# powerBus_Sch.net
KiCad netlist of a schematic drawn in Altium Designer
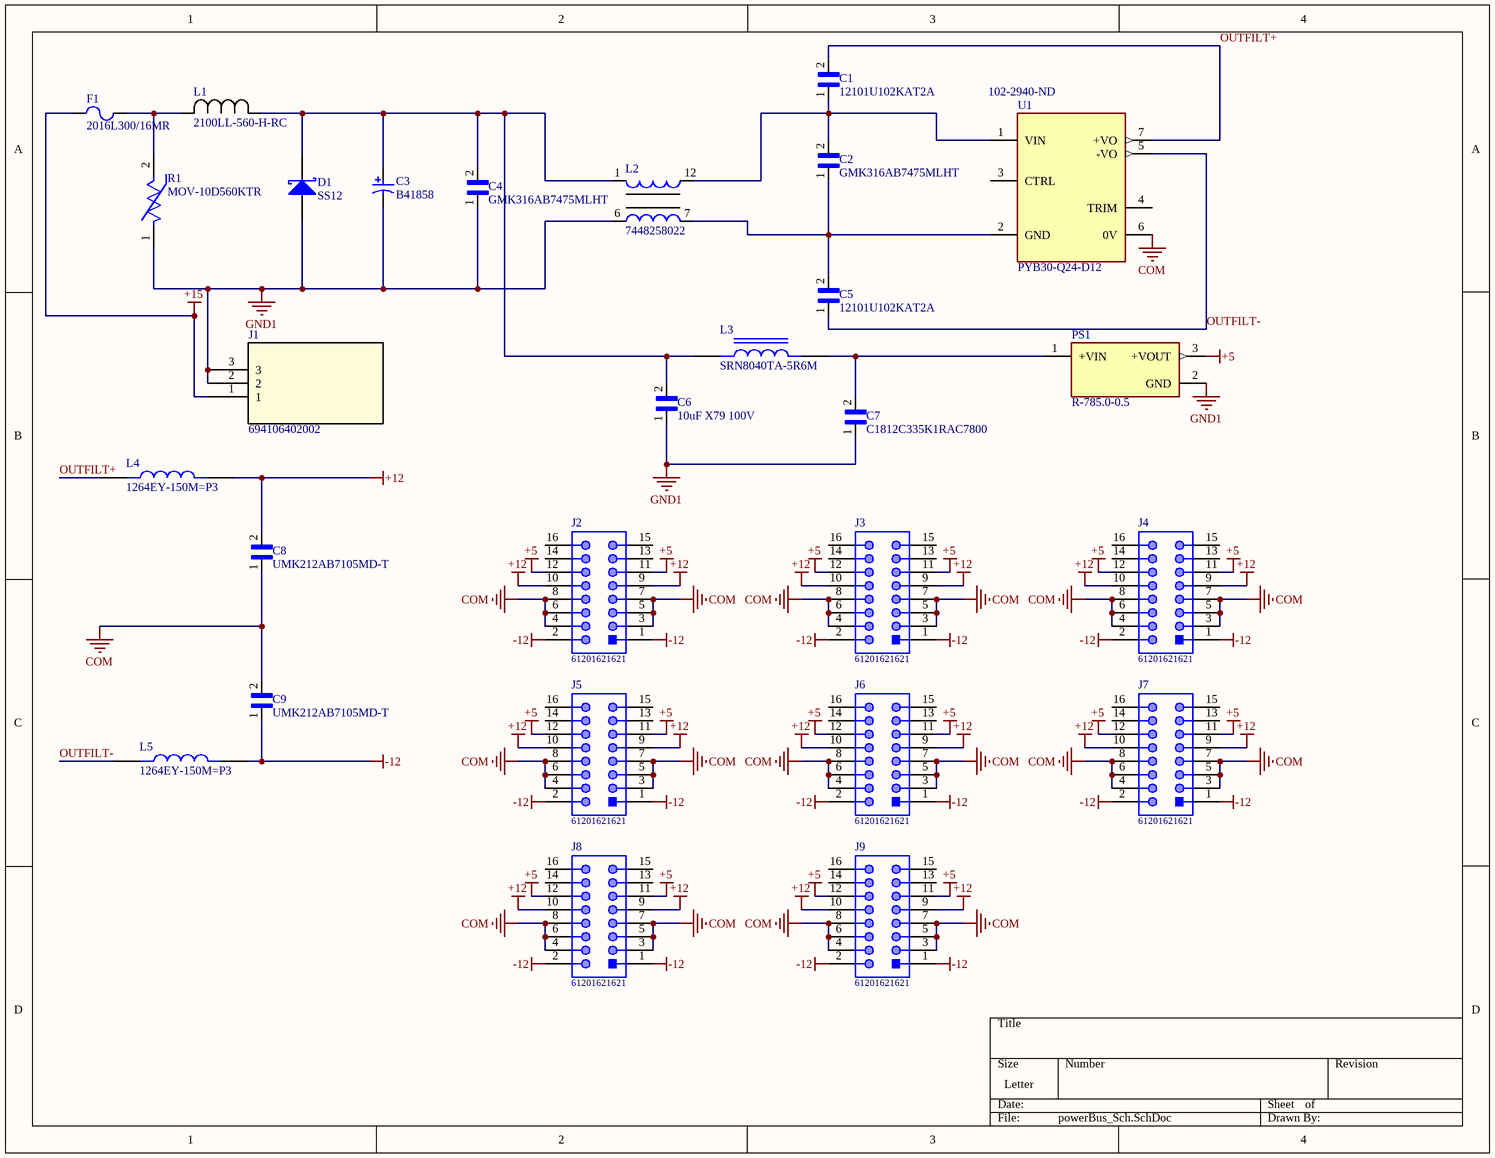
[diagram p0: powerBus_Sch.SchDoc]

(export (version "E")
  (design (tool "Eeschema 10.0.6"))
  (components
    (comp (ref "C1")
      (value "12101U102KAT2A")
      (footprint "CAPC3224X140N")
      (description "1210 1 nF 100 V Â±10 % Tolerance SMT Ultra Low ESR RF/Microwave Capacitor")
      (libsource (lib "1000pf_NP0_lowesr_1210") (part "12101U102KAT2A"))
    )
    (comp (ref "C2")
      (value "GMK316AB7475MLHT")
      (footprint "CAPC3216X180N")
      (description "0")
      (libsource (lib "4R7_X7R_1206_GMK316AB7475MLHT") (part "GMK316AB7475MLHT"))
    )
    (comp (ref "C3")
      (value "B41858")
      (footprint "CAPPR65-350-1150X800X1250")
      (description "Aluminum Electrolytic Capacitor, 120uF")
      (libsource (lib "Altium Content Vault") (part "CAP-P-2"))
    )
    (comp (ref "C4")
      (value "GMK316AB7475MLHT")
      (footprint "CAPC3216X180N")
      (description "0")
      (libsource (lib "4R7_X7R_1206_GMK316AB7475MLHT") (part "GMK316AB7475MLHT"))
    )
    (comp (ref "C5")
      (value "12101U102KAT2A")
      (footprint "CAPC3224X140N")
      (description "1210 1 nF 100 V Â±10 % Tolerance SMT Ultra Low ESR RF/Microwave Capacitor")
      (libsource (lib "1000pf_NP0_lowesr_1210") (part "12101U102KAT2A"))
    )
    (comp (ref "C6")
      (value "10uF X79 100V")
      (footprint "CAPC5750X330N")
      (fields (field (name "MP") "C1812C335K1RAC7800"))
      (libsource (lib "3.3uF_kemet_x7R_C1812C335K1RAC7800") (part "C1812C335K1RAC7800"))
    )
    (comp (ref "C7")
      (value "C1812C335K1RAC7800")
      (footprint "CAPC4532X210N")
      (libsource (lib "3.3uF_kemet_x7R_C1812C335K1RAC7800") (part "C1812C335K1RAC7800"))
    )
    (comp (ref "C8")
      (value "UMK212AB7105MD-T")
      (footprint "CAPC2013X95N")
      (description "CAP ,MLCC ,0805,50V ,X7R,1.0UF20% ,T&R")
      (libsource (lib "1uF_X7R_low_esr_UMK212AB7105MD-T") (part "UMK212AB7105MD-T"))
    )
    (comp (ref "C9")
      (value "UMK212AB7105MD-T")
      (footprint "CAPC2013X95N")
      (description "CAP ,MLCC ,0805,50V ,X7R,1.0UF20% ,T&R")
      (libsource (lib "1uF_X7R_low_esr_UMK212AB7105MD-T") (part "UMK212AB7105MD-T"))
    )
    (comp (ref "D1")
      (value "SS12")
      (footprint "FAIR-DO-214AC-2_V")
      (description "Schottky Rectifier, 20 V, 1 A, -65 to 125 degC, 2-Pin DO-214AC, RoHS, Tape and Reel")
      (fields (field (name "MANUFACTURER") "Fairchild"))
      (libsource (lib "Ryan Laur") (part "DSKY-AK-2"))
    )
    (comp (ref "F1")
      (value "2016L300/16MR")
      (footprint "LFUS-2016L050MR_V")
      (description "Poly-Fuse(R) Resettable PTC, 60 V, 20 A, -40 to 85 degC, 2-Pin SMD, RoHS, Tape and Reel")
      (fields (field (name "MANUFACTURER") "Littelfuse"))
      (libsource (lib "Altium Content Vault") (part "FUSE-2"))
    )
    (comp (ref "J1")
      (value "694106402002")
      (footprint "DC_JACK")
      (description "No Description Available")
      (fields (field (name "COPYRIGHT") "Copyright (C) 2022 Ultra Librarian. All rights reserved."))
      (libsource (lib "wurth_dc_jack_694106402002") (part "694106402002"))
    )
    (comp (ref "J2")
      (value "61201621621")
      (footprint "61201621621")
      (description "Male Box Header WR-BHD, THT, Vertical, pitch 2.54 mm, 16 pins")
      (fields (field (name "MANUFACTURER") "Wurth Elektronik") (field (name "PUBLISHER") "WurthElektronik"))
      (libsource (lib "Altium Content Vault") (part "WE-CN-2P-M-R16"))
    )
    (comp (ref "J3")
      (value "61201621621")
      (footprint "61201621621")
      (description "Male Box Header WR-BHD, THT, Vertical, pitch 2.54 mm, 16 pins")
      (fields (field (name "MANUFACTURER") "Wurth Elektronik") (field (name "PUBLISHER") "WurthElektronik"))
      (libsource (lib "Altium Content Vault") (part "WE-CN-2P-M-R16"))
    )
    (comp (ref "J4")
      (value "61201621621")
      (footprint "61201621621")
      (description "Male Box Header WR-BHD, THT, Vertical, pitch 2.54 mm, 16 pins")
      (fields (field (name "MANUFACTURER") "Wurth Elektronik") (field (name "PUBLISHER") "WurthElektronik"))
      (libsource (lib "Altium Content Vault") (part "WE-CN-2P-M-R16"))
    )
    (comp (ref "J5")
      (value "61201621621")
      (footprint "61201621621")
      (description "Male Box Header WR-BHD, THT, Vertical, pitch 2.54 mm, 16 pins")
      (fields (field (name "MANUFACTURER") "Wurth Elektronik") (field (name "PUBLISHER") "WurthElektronik"))
      (libsource (lib "Altium Content Vault") (part "WE-CN-2P-M-R16"))
    )
    (comp (ref "J6")
      (value "61201621621")
      (footprint "61201621621")
      (description "Male Box Header WR-BHD, THT, Vertical, pitch 2.54 mm, 16 pins")
      (fields (field (name "MANUFACTURER") "Wurth Elektronik") (field (name "PUBLISHER") "WurthElektronik"))
      (libsource (lib "Altium Content Vault") (part "WE-CN-2P-M-R16"))
    )
    (comp (ref "J7")
      (value "61201621621")
      (footprint "61201621621")
      (description "Male Box Header WR-BHD, THT, Vertical, pitch 2.54 mm, 16 pins")
      (fields (field (name "MANUFACTURER") "Wurth Elektronik") (field (name "PUBLISHER") "WurthElektronik"))
      (libsource (lib "Altium Content Vault") (part "WE-CN-2P-M-R16"))
    )
    (comp (ref "J8")
      (value "61201621621")
      (footprint "61201621621")
      (description "Male Box Header WR-BHD, THT, Vertical, pitch 2.54 mm, 16 pins")
      (fields (field (name "MANUFACTURER") "Wurth Elektronik") (field (name "PUBLISHER") "WurthElektronik"))
      (libsource (lib "Altium Content Vault") (part "WE-CN-2P-M-R16"))
    )
    (comp (ref "J9")
      (value "61201621621")
      (footprint "61201621621")
      (description "Male Box Header WR-BHD, THT, Vertical, pitch 2.54 mm, 16 pins")
      (fields (field (name "MANUFACTURER") "Wurth Elektronik") (field (name "PUBLISHER") "WurthElektronik"))
      (libsource (lib "Altium Content Vault") (part "WE-CN-2P-M-R16"))
    )
    (comp (ref "L1")
      (value "2100LL-560-H-RC")
      (footprint "IND_2100LL_34_H")
      (description "No Description Available")
      (fields (field (name "COPYRIGHT") "Copyright (C) 2022 Ultra Librarian. All rights reserved."))
      (libsource (lib "2100LL-560-H-RC") (part "2100LL-560-H-RC"))
    )
    (comp (ref "L2")
      (value "7448258022")
      (footprint "WE-CMB-XL")
      (description "THT Common Mode Power Line Choke WE-CMB, L = 2.20 mH")
      (libsource (lib "Altium Content Vault") (part "PAS-IND-INDUCTOR-4G"))
    )
    (comp (ref "L3")
      (value "SRN8040TA-5R6M")
      (footprint "IND_SRN8040TA-5R6M")
      (libsource (lib "SRN8040TA-5R6M") (part "SRN8040TA-5R6M"))
    )
    (comp (ref "L4")
      (value "1264EY-150M=P3")
      (footprint "IND_1264EY-150M=P3")
      (description "Inductor Power Shielded Wirewound 22uH 20% 100KHz Ferrite 1.8A 132mOhm DCR 2424 T/R")
      (libsource (lib "murata_15uh_ferrite_ind_1264EY-150M_P3") (part "1264EY-150M=P3"))
    )
    (comp (ref "L5")
      (value "1264EY-150M=P3")
      (footprint "IND_1264EY-150M=P3")
      (description "Inductor Power Shielded Wirewound 22uH 20% 100KHz Ferrite 1.8A 132mOhm DCR 2424 T/R")
      (libsource (lib "murata_15uh_ferrite_ind_1264EY-150M_P3") (part "1264EY-150M=P3"))
    )
    (comp (ref "PS1")
      (value "R-785.0-0.5")
      (footprint "CONV_R-785.0-0.5")
      (description "0.5A DC/DC-Converter 'INNOLINE' SIP3 reg")
      (fields (field (name "MF") "Recom Power"))
      (libsource (lib "Recom-785.0 5V-0.5A") (part "R-785.0-0.5"))
    )
    (comp (ref "R1")
      (value "MOV-10D560KTR")
      (footprint "FP-MOV-10D201KTR-MFG")
      (description "VARISTOR 200V 2.5KA DISC 10MM")
      (fields
        (field (name "MANUFACTURER") "Bourns Inc.")
        (field (name "OCTOPART") "https://octopart.com/mov-10d201ktr-bourns-19184757")
      )
      (libsource (lib "Altium Content Vault") (part "78a88060d5b7b043d6e48adc4284376"))
    )
    (comp (ref "U1")
      (value "PYB30-Q24-D12")
      (footprint "CONV_PYB30-Q24-D12")
      (description "12/-12 Vdc, 1.25 A, 30 W, 9~36 Vdc Input Range")
      (fields (field (name "SUPPLIER PART NUMBER 1") "102-2940-ND"))
      (libsource (lib "DC_Conv_PYB30-Q24-D12") (part "PYB30-Q24-D12"))
    )
  )
  (nets
    (net (code "1") (name "+5") (class "Default")
      (node (ref "J2") (pin "11") (pinfunction "11_11") (pintype "passive"))
      (node (ref "J2") (pin "12") (pinfunction "12_12") (pintype "passive"))
      (node (ref "J3") (pin "11") (pinfunction "11_11") (pintype "passive"))
      (node (ref "J3") (pin "12") (pinfunction "12_12") (pintype "passive"))
      (node (ref "J4") (pin "11") (pinfunction "11_11") (pintype "passive"))
      (node (ref "J4") (pin "12") (pinfunction "12_12") (pintype "passive"))
      (node (ref "J5") (pin "11") (pinfunction "11_11") (pintype "passive"))
      (node (ref "J5") (pin "12") (pinfunction "12_12") (pintype "passive"))
      (node (ref "J6") (pin "11") (pinfunction "11_11") (pintype "passive"))
      (node (ref "J6") (pin "12") (pinfunction "12_12") (pintype "passive"))
      (node (ref "J7") (pin "11") (pinfunction "11_11") (pintype "passive"))
      (node (ref "J7") (pin "12") (pinfunction "12_12") (pintype "passive"))
      (node (ref "J8") (pin "11") (pinfunction "11_11") (pintype "passive"))
      (node (ref "J8") (pin "12") (pinfunction "12_12") (pintype "passive"))
      (node (ref "J9") (pin "11") (pinfunction "11_11") (pintype "passive"))
      (node (ref "J9") (pin "12") (pinfunction "12_12") (pintype "passive"))
      (node (ref "PS1") (pin "3") (pinfunction "+VOUT_3") (pintype "output"))
    )
    (net (code "2") (name "+12") (class "Default")
      (node (ref "C8") (pin "2") (pinfunction "2_2") (pintype "passive"))
      (node (ref "J2") (pin "10") (pinfunction "10_10") (pintype "passive"))
      (node (ref "J2") (pin "9") (pinfunction "9_9") (pintype "passive"))
      (node (ref "J3") (pin "10") (pinfunction "10_10") (pintype "passive"))
      (node (ref "J3") (pin "9") (pinfunction "9_9") (pintype "passive"))
      (node (ref "J4") (pin "10") (pinfunction "10_10") (pintype "passive"))
      (node (ref "J4") (pin "9") (pinfunction "9_9") (pintype "passive"))
      (node (ref "J5") (pin "10") (pinfunction "10_10") (pintype "passive"))
      (node (ref "J5") (pin "9") (pinfunction "9_9") (pintype "passive"))
      (node (ref "J6") (pin "10") (pinfunction "10_10") (pintype "passive"))
      (node (ref "J6") (pin "9") (pinfunction "9_9") (pintype "passive"))
      (node (ref "J7") (pin "10") (pinfunction "10_10") (pintype "passive"))
      (node (ref "J7") (pin "9") (pinfunction "9_9") (pintype "passive"))
      (node (ref "J8") (pin "10") (pinfunction "10_10") (pintype "passive"))
      (node (ref "J8") (pin "9") (pinfunction "9_9") (pintype "passive"))
      (node (ref "J9") (pin "10") (pinfunction "10_10") (pintype "passive"))
      (node (ref "J9") (pin "9") (pinfunction "9_9") (pintype "passive"))
      (node (ref "L4") (pin "2") (pinfunction "2_2") (pintype "passive"))
    )
    (net (code "3") (name "+15") (class "Default")
      (node (ref "F1") (pin "1") (pinfunction "1_1") (pintype "passive"))
      (node (ref "J1") (pin "1") (pinfunction "1_1") (pintype "passive"))
    )
    (net (code "4") (name "-12") (class "Default")
      (node (ref "C9") (pin "1") (pinfunction "1_1") (pintype "passive"))
      (node (ref "J2") (pin "1") (pinfunction "1_1") (pintype "passive"))
      (node (ref "J2") (pin "2") (pinfunction "2_2") (pintype "passive"))
      (node (ref "J3") (pin "1") (pinfunction "1_1") (pintype "passive"))
      (node (ref "J3") (pin "2") (pinfunction "2_2") (pintype "passive"))
      (node (ref "J4") (pin "1") (pinfunction "1_1") (pintype "passive"))
      (node (ref "J4") (pin "2") (pinfunction "2_2") (pintype "passive"))
      (node (ref "J5") (pin "1") (pinfunction "1_1") (pintype "passive"))
      (node (ref "J5") (pin "2") (pinfunction "2_2") (pintype "passive"))
      (node (ref "J6") (pin "1") (pinfunction "1_1") (pintype "passive"))
      (node (ref "J6") (pin "2") (pinfunction "2_2") (pintype "passive"))
      (node (ref "J7") (pin "1") (pinfunction "1_1") (pintype "passive"))
      (node (ref "J7") (pin "2") (pinfunction "2_2") (pintype "passive"))
      (node (ref "J8") (pin "1") (pinfunction "1_1") (pintype "passive"))
      (node (ref "J8") (pin "2") (pinfunction "2_2") (pintype "passive"))
      (node (ref "J9") (pin "1") (pinfunction "1_1") (pintype "passive"))
      (node (ref "J9") (pin "2") (pinfunction "2_2") (pintype "passive"))
      (node (ref "L5") (pin "2") (pinfunction "2_2") (pintype "passive"))
    )
    (net (code "5") (name "/OUTFILT+") (class "Default")
      (node (ref "C1") (pin "2") (pinfunction "2_2") (pintype "passive"))
      (node (ref "L4") (pin "1") (pinfunction "1_1") (pintype "passive"))
      (node (ref "U1") (pin "7") (pinfunction "+VO_7") (pintype "output"))
    )
    (net (code "6") (name "/OUTFILT-") (class "Default")
      (node (ref "C5") (pin "1") (pinfunction "1_1") (pintype "passive"))
      (node (ref "L5") (pin "1") (pinfunction "1_1") (pintype "passive"))
      (node (ref "U1") (pin "5") (pinfunction "-VO_5") (pintype "output"))
    )
    (net (code "7") (name "COM") (class "Default")
      (node (ref "C8") (pin "1") (pinfunction "1_1") (pintype "passive"))
      (node (ref "C9") (pin "2") (pinfunction "2_2") (pintype "passive"))
      (node (ref "J2") (pin "3") (pinfunction "3_3") (pintype "passive"))
      (node (ref "J2") (pin "4") (pinfunction "4_4") (pintype "passive"))
      (node (ref "J2") (pin "5") (pinfunction "5_5") (pintype "passive"))
      (node (ref "J2") (pin "6") (pinfunction "6_6") (pintype "passive"))
      (node (ref "J2") (pin "7") (pinfunction "7_7") (pintype "passive"))
      (node (ref "J2") (pin "8") (pinfunction "8_8") (pintype "passive"))
      (node (ref "J3") (pin "3") (pinfunction "3_3") (pintype "passive"))
      (node (ref "J3") (pin "4") (pinfunction "4_4") (pintype "passive"))
      (node (ref "J3") (pin "5") (pinfunction "5_5") (pintype "passive"))
      (node (ref "J3") (pin "6") (pinfunction "6_6") (pintype "passive"))
      (node (ref "J3") (pin "7") (pinfunction "7_7") (pintype "passive"))
      (node (ref "J3") (pin "8") (pinfunction "8_8") (pintype "passive"))
      (node (ref "J4") (pin "3") (pinfunction "3_3") (pintype "passive"))
      (node (ref "J4") (pin "4") (pinfunction "4_4") (pintype "passive"))
      (node (ref "J4") (pin "5") (pinfunction "5_5") (pintype "passive"))
      (node (ref "J4") (pin "6") (pinfunction "6_6") (pintype "passive"))
      (node (ref "J4") (pin "7") (pinfunction "7_7") (pintype "passive"))
      (node (ref "J4") (pin "8") (pinfunction "8_8") (pintype "passive"))
      (node (ref "J5") (pin "3") (pinfunction "3_3") (pintype "passive"))
      (node (ref "J5") (pin "4") (pinfunction "4_4") (pintype "passive"))
      (node (ref "J5") (pin "5") (pinfunction "5_5") (pintype "passive"))
      (node (ref "J5") (pin "6") (pinfunction "6_6") (pintype "passive"))
      (node (ref "J5") (pin "7") (pinfunction "7_7") (pintype "passive"))
      (node (ref "J5") (pin "8") (pinfunction "8_8") (pintype "passive"))
      (node (ref "J6") (pin "3") (pinfunction "3_3") (pintype "passive"))
      (node (ref "J6") (pin "4") (pinfunction "4_4") (pintype "passive"))
      (node (ref "J6") (pin "5") (pinfunction "5_5") (pintype "passive"))
      (node (ref "J6") (pin "6") (pinfunction "6_6") (pintype "passive"))
      (node (ref "J6") (pin "7") (pinfunction "7_7") (pintype "passive"))
      (node (ref "J6") (pin "8") (pinfunction "8_8") (pintype "passive"))
      (node (ref "J7") (pin "3") (pinfunction "3_3") (pintype "passive"))
      (node (ref "J7") (pin "4") (pinfunction "4_4") (pintype "passive"))
      (node (ref "J7") (pin "5") (pinfunction "5_5") (pintype "passive"))
      (node (ref "J7") (pin "6") (pinfunction "6_6") (pintype "passive"))
      (node (ref "J7") (pin "7") (pinfunction "7_7") (pintype "passive"))
      (node (ref "J7") (pin "8") (pinfunction "8_8") (pintype "passive"))
      (node (ref "J8") (pin "3") (pinfunction "3_3") (pintype "passive"))
      (node (ref "J8") (pin "4") (pinfunction "4_4") (pintype "passive"))
      (node (ref "J8") (pin "5") (pinfunction "5_5") (pintype "passive"))
      (node (ref "J8") (pin "6") (pinfunction "6_6") (pintype "passive"))
      (node (ref "J8") (pin "7") (pinfunction "7_7") (pintype "passive"))
      (node (ref "J8") (pin "8") (pinfunction "8_8") (pintype "passive"))
      (node (ref "J9") (pin "3") (pinfunction "3_3") (pintype "passive"))
      (node (ref "J9") (pin "4") (pinfunction "4_4") (pintype "passive"))
      (node (ref "J9") (pin "5") (pinfunction "5_5") (pintype "passive"))
      (node (ref "J9") (pin "6") (pinfunction "6_6") (pintype "passive"))
      (node (ref "J9") (pin "7") (pinfunction "7_7") (pintype "passive"))
      (node (ref "J9") (pin "8") (pinfunction "8_8") (pintype "passive"))
      (node (ref "U1") (pin "6") (pinfunction "0V_6") (pintype "power_in"))
    )
    (net (code "8") (name "GND1") (class "Default")
      (node (ref "C3") (pin "2") (pinfunction "2_2") (pintype "passive"))
      (node (ref "C4") (pin "1") (pinfunction "1_1") (pintype "passive"))
      (node (ref "C6") (pin "1") (pinfunction "1_1") (pintype "passive"))
      (node (ref "C7") (pin "1") (pinfunction "1_1") (pintype "passive"))
      (node (ref "D1") (pin "1") (pinfunction "A_1") (pintype "passive"))
      (node (ref "J1") (pin "2") (pinfunction "2_2") (pintype "passive"))
      (node (ref "J1") (pin "3") (pinfunction "3_3") (pintype "passive"))
      (node (ref "L2") (pin "6") (pinfunction "6_6") (pintype "passive"))
      (node (ref "PS1") (pin "2") (pinfunction "GND_2") (pintype "power_in"))
      (node (ref "R1") (pin "1") (pinfunction "1_1") (pintype "passive"))
    )
    (net (code "9") (name "Net-(D1-K)") (class "Default")
      (node (ref "C3") (pin "1") (pinfunction "1_1") (pintype "passive"))
      (node (ref "C4") (pin "2") (pinfunction "2_2") (pintype "passive"))
      (node (ref "C6") (pin "2") (pinfunction "2_2") (pintype "passive"))
      (node (ref "D1") (pin "2") (pinfunction "K_2") (pintype "passive"))
      (node (ref "L1") (pin "1") (pinfunction "1_1") (pintype "passive"))
      (node (ref "L2") (pin "1") (pinfunction "1_1") (pintype "passive"))
      (node (ref "L3") (pin "1") (pinfunction "1_1") (pintype "passive"))
    )
    (net (code "10") (name "Net-(F1-Pad2)") (class "Default")
      (node (ref "F1") (pin "2") (pinfunction "2_2") (pintype "passive"))
      (node (ref "L1") (pin "2") (pinfunction "2_2") (pintype "passive"))
      (node (ref "R1") (pin "2") (pinfunction "2_2") (pintype "passive"))
    )
    (net (code "11") (name "Net-(PS1-+VIN)") (class "Default")
      (node (ref "C7") (pin "2") (pinfunction "2_2") (pintype "passive"))
      (node (ref "L3") (pin "2") (pinfunction "2_2") (pintype "passive"))
      (node (ref "PS1") (pin "1") (pinfunction "+VIN_1") (pintype "power_in"))
    )
    (net (code "12") (name "Net-(U1-GND)") (class "Default")
      (node (ref "C2") (pin "1") (pinfunction "1_1") (pintype "passive"))
      (node (ref "C5") (pin "2") (pinfunction "2_2") (pintype "passive"))
      (node (ref "L2") (pin "7") (pinfunction "7_7") (pintype "passive"))
      (node (ref "U1") (pin "2") (pinfunction "GND_2") (pintype "power_in"))
    )
    (net (code "13") (name "Net-(U1-VIN)") (class "Default")
      (node (ref "C1") (pin "1") (pinfunction "1_1") (pintype "passive"))
      (node (ref "C2") (pin "2") (pinfunction "2_2") (pintype "passive"))
      (node (ref "L2") (pin "12") (pinfunction "12_12") (pintype "passive"))
      (node (ref "U1") (pin "1") (pinfunction "VIN_1") (pintype "power_in"))
    )
    (net (code "14") (name "unconnected-(J2-Pad13)") (class "Default")
      (node (ref "J2") (pin "13") (pinfunction "13_13") (pintype "passive"))
    )
    (net (code "15") (name "unconnected-(J2-Pad14)") (class "Default")
      (node (ref "J2") (pin "14") (pinfunction "14_14") (pintype "passive"))
    )
    (net (code "16") (name "unconnected-(J2-Pad15)") (class "Default")
      (node (ref "J2") (pin "15") (pinfunction "15_15") (pintype "passive"))
    )
    (net (code "17") (name "unconnected-(J2-Pad16)") (class "Default")
      (node (ref "J2") (pin "16") (pinfunction "16_16") (pintype "passive"))
    )
    (net (code "18") (name "unconnected-(J3-Pad13)") (class "Default")
      (node (ref "J3") (pin "13") (pinfunction "13_13") (pintype "passive"))
    )
    (net (code "19") (name "unconnected-(J3-Pad14)") (class "Default")
      (node (ref "J3") (pin "14") (pinfunction "14_14") (pintype "passive"))
    )
    (net (code "20") (name "unconnected-(J3-Pad15)") (class "Default")
      (node (ref "J3") (pin "15") (pinfunction "15_15") (pintype "passive"))
    )
    (net (code "21") (name "unconnected-(J3-Pad16)") (class "Default")
      (node (ref "J3") (pin "16") (pinfunction "16_16") (pintype "passive"))
    )
    (net (code "22") (name "unconnected-(J4-Pad13)") (class "Default")
      (node (ref "J4") (pin "13") (pinfunction "13_13") (pintype "passive"))
    )
    (net (code "23") (name "unconnected-(J4-Pad14)") (class "Default")
      (node (ref "J4") (pin "14") (pinfunction "14_14") (pintype "passive"))
    )
    (net (code "24") (name "unconnected-(J4-Pad15)") (class "Default")
      (node (ref "J4") (pin "15") (pinfunction "15_15") (pintype "passive"))
    )
    (net (code "25") (name "unconnected-(J4-Pad16)") (class "Default")
      (node (ref "J4") (pin "16") (pinfunction "16_16") (pintype "passive"))
    )
    (net (code "26") (name "unconnected-(J5-Pad13)") (class "Default")
      (node (ref "J5") (pin "13") (pinfunction "13_13") (pintype "passive"))
    )
    (net (code "27") (name "unconnected-(J5-Pad14)") (class "Default")
      (node (ref "J5") (pin "14") (pinfunction "14_14") (pintype "passive"))
    )
    (net (code "28") (name "unconnected-(J5-Pad15)") (class "Default")
      (node (ref "J5") (pin "15") (pinfunction "15_15") (pintype "passive"))
    )
    (net (code "29") (name "unconnected-(J5-Pad16)") (class "Default")
      (node (ref "J5") (pin "16") (pinfunction "16_16") (pintype "passive"))
    )
    (net (code "30") (name "unconnected-(J6-Pad13)") (class "Default")
      (node (ref "J6") (pin "13") (pinfunction "13_13") (pintype "passive"))
    )
    (net (code "31") (name "unconnected-(J6-Pad14)") (class "Default")
      (node (ref "J6") (pin "14") (pinfunction "14_14") (pintype "passive"))
    )
    (net (code "32") (name "unconnected-(J6-Pad15)") (class "Default")
      (node (ref "J6") (pin "15") (pinfunction "15_15") (pintype "passive"))
    )
    (net (code "33") (name "unconnected-(J6-Pad16)") (class "Default")
      (node (ref "J6") (pin "16") (pinfunction "16_16") (pintype "passive"))
    )
    (net (code "34") (name "unconnected-(J7-Pad13)") (class "Default")
      (node (ref "J7") (pin "13") (pinfunction "13_13") (pintype "passive"))
    )
    (net (code "35") (name "unconnected-(J7-Pad14)") (class "Default")
      (node (ref "J7") (pin "14") (pinfunction "14_14") (pintype "passive"))
    )
    (net (code "36") (name "unconnected-(J7-Pad15)") (class "Default")
      (node (ref "J7") (pin "15") (pinfunction "15_15") (pintype "passive"))
    )
    (net (code "37") (name "unconnected-(J7-Pad16)") (class "Default")
      (node (ref "J7") (pin "16") (pinfunction "16_16") (pintype "passive"))
    )
    (net (code "38") (name "unconnected-(J8-Pad13)") (class "Default")
      (node (ref "J8") (pin "13") (pinfunction "13_13") (pintype "passive"))
    )
    (net (code "39") (name "unconnected-(J8-Pad14)") (class "Default")
      (node (ref "J8") (pin "14") (pinfunction "14_14") (pintype "passive"))
    )
    (net (code "40") (name "unconnected-(J8-Pad15)") (class "Default")
      (node (ref "J8") (pin "15") (pinfunction "15_15") (pintype "passive"))
    )
    (net (code "41") (name "unconnected-(J8-Pad16)") (class "Default")
      (node (ref "J8") (pin "16") (pinfunction "16_16") (pintype "passive"))
    )
    (net (code "42") (name "unconnected-(J9-Pad13)") (class "Default")
      (node (ref "J9") (pin "13") (pinfunction "13_13") (pintype "passive"))
    )
    (net (code "43") (name "unconnected-(J9-Pad14)") (class "Default")
      (node (ref "J9") (pin "14") (pinfunction "14_14") (pintype "passive"))
    )
    (net (code "44") (name "unconnected-(J9-Pad15)") (class "Default")
      (node (ref "J9") (pin "15") (pinfunction "15_15") (pintype "passive"))
    )
    (net (code "45") (name "unconnected-(J9-Pad16)") (class "Default")
      (node (ref "J9") (pin "16") (pinfunction "16_16") (pintype "passive"))
    )
    (net (code "46") (name "unconnected-(U1-CTRL-Pad3)") (class "Default")
      (node (ref "U1") (pin "3") (pinfunction "CTRL_3") (pintype "passive"))
    )
    (net (code "47") (name "unconnected-(U1-TRIM-Pad4)") (class "Default")
      (node (ref "U1") (pin "4") (pinfunction "TRIM_4") (pintype "passive"))
    )
  )
)
